# Sheet1.net
KiCad netlist of a schematic drawn in Altium Designer
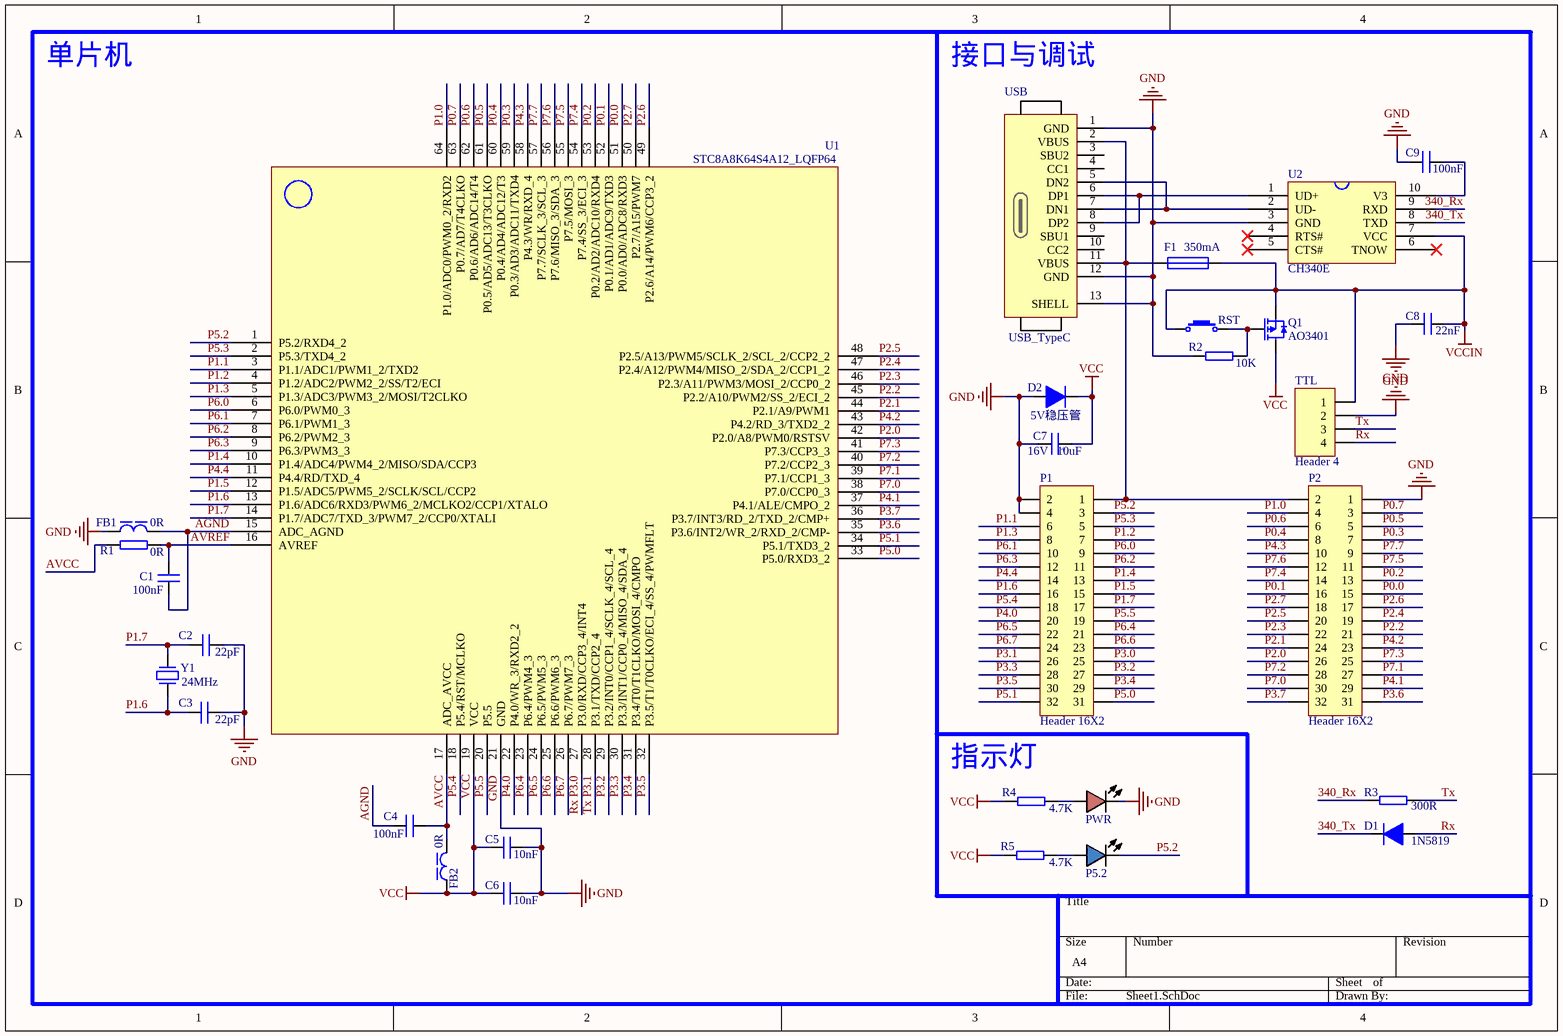
[diagram p0: Sheet1.SchDoc]

(export (version "E")
  (design (tool "Eeschema 10.0.6"))
  (components
    (comp (ref "C1")
      (value "100nF")
      (footprint "0603电容")
      (description "电容")
      (fields (field (name "版权归属") "源创客"))
      (libsource (lib "Schlib1") (part "Capacitor"))
    )
    (comp (ref "C2")
      (value "22pF")
      (footprint "0603电容")
      (description "电容")
      (fields (field (name "版权归属") "源创客"))
      (libsource (lib "Schlib1") (part "Capacitor"))
    )
    (comp (ref "C3")
      (value "22pF")
      (footprint "0603电容")
      (description "电容")
      (fields (field (name "版权归属") "源创客"))
      (libsource (lib "Schlib1") (part "Capacitor"))
    )
    (comp (ref "C4")
      (value "100nF")
      (footprint "0603电容")
      (description "电容")
      (fields (field (name "版权归属") "源创客"))
      (libsource (lib "Schlib1") (part "Capacitor"))
    )
    (comp (ref "C5")
      (value "10nF")
      (footprint "0603电容")
      (description "电容")
      (fields (field (name "版权归属") "源创客"))
      (libsource (lib "Schlib1") (part "Capacitor"))
    )
    (comp (ref "C6")
      (value "10nF")
      (footprint "0603电容")
      (description "电容")
      (fields (field (name "版权归属") "源创客"))
      (libsource (lib "Schlib1") (part "Capacitor"))
    )
    (comp (ref "C7")
      (value "16V   10uF")
      (footprint "Tan1206")
      (description "贴片钽电容")
      (fields (field (name "版权归属") "源创客"))
      (libsource (lib "Schlib1") (part "T_Capacitor"))
    )
    (comp (ref "C8")
      (value "22nF")
      (footprint "0603电容")
      (description "电容")
      (fields (field (name "版权归属") "源创客"))
      (libsource (lib "Schlib1") (part "Capacitor"))
    )
    (comp (ref "C9")
      (value "100nF")
      (footprint "0603电容")
      (description "电容")
      (fields (field (name "版权归属") "源创客"))
      (libsource (lib "Schlib1") (part "Capacitor"))
    )
    (comp (ref "D1") (value "1N5819") (footprint "SOD-323") (libsource (lib "Schlib1") (part "1N5819")))
    (comp (ref "D2") (value "5V稳压管") (footprint "SOD-323") (libsource (lib "Schlib1") (part "5V稳压管")))
    (comp (ref "F1")
      (value "350mA")
      (footprint "0603保险丝")
      (description "Fuse")
      (libsource (lib "Schlib1") (part "Fuse"))
    )
    (comp (ref "FB1")
      (value "0R")
      (footprint "0603磁珠")
      (description "磁珠")
      (libsource (lib "Schlib1") (part "FERRITE_BEAD"))
    )
    (comp (ref "FB2")
      (value "0R")
      (footprint "0603磁珠")
      (description "磁珠")
      (libsource (lib "Schlib1") (part "FERRITE_BEAD"))
    )
    (comp (ref "P1")
      (value "Header 16X2")
      (footprint "HDR-16X2")
      (description "16*2P接插件")
      (fields (field (name "版权归属") "源创客"))
      (libsource (lib "Schlib1") (part "Header 16X2"))
    )
    (comp (ref "P2")
      (value "Header 16X2")
      (footprint "HDR-16X2")
      (description "16*2P接插件")
      (fields (field (name "版权归属") "源创客"))
      (libsource (lib "Schlib1") (part "Header 16X2"))
    )
    (comp (ref "P5.2")
      (value "Blue_LED")
      (footprint "LED 0603B")
      (libsource (lib "Schlib1") (part "Blue_LED"))
    )
    (comp (ref "PWR") (value "Red_LED") (footprint "LED 0603R") (libsource (lib "Schlib1") (part "Red_LED")))
    (comp (ref "Q1")
      (value "AO3401")
      (footprint "SOT-23")
      (fields (field (name "版权归属") "源创客"))
      (libsource (lib "Schlib1") (part "AO3401"))
    )
    (comp (ref "R1")
      (value "0R")
      (footprint "0603电阻")
      (description "电阻")
      (fields (field (name "版权归属") "源创客"))
      (libsource (lib "Schlib1") (part "Resistor"))
    )
    (comp (ref "R2")
      (value "10K")
      (footprint "0603电阻")
      (description "电阻")
      (fields (field (name "版权归属") "源创客"))
      (libsource (lib "Schlib1") (part "Resistor"))
    )
    (comp (ref "R3")
      (value "300R")
      (footprint "0603电阻")
      (description "电阻")
      (fields (field (name "版权归属") "源创客"))
      (libsource (lib "Schlib1") (part "Resistor"))
    )
    (comp (ref "R4")
      (value "4.7K")
      (footprint "0603电阻")
      (description "电阻")
      (fields (field (name "版权归属") "源创客"))
      (libsource (lib "Schlib1") (part "Resistor"))
    )
    (comp (ref "R5")
      (value "4.7K")
      (footprint "0603电阻")
      (description "电阻")
      (fields (field (name "版权归属") "源创客"))
      (libsource (lib "Schlib1") (part "Resistor"))
    )
    (comp (ref "RST")
      (value "*")
      (footprint "SWD")
      (description "轻触开关")
      (libsource (lib "Schlib1") (part "SW_TB"))
    )
    (comp (ref "TTL")
      (value "Header 4")
      (footprint "HDR-1X4")
      (description "4P接插件")
      (fields (field (name "版权归属") "源创客"))
      (libsource (lib "Schlib1") (part "Header 4"))
    )
    (comp (ref "U1")
      (value "STC8A8K64S4A12_LQFP64")
      (footprint "LQFP64-10*10")
      (libsource (lib "Schlib1") (part "STC8A8K64S4A12_LQFP64"))
    )
    (comp (ref "U2") (value "CH340E") (footprint "MSOP-10") (libsource (lib "Schlib1") (part "CH340E")))
    (comp (ref "USB")
      (value "USB_TypeC")
      (footprint "USB3.1 TypeC")
      (description "TypeC接口")
      (libsource (lib "Schlib1") (part "USB3.1"))
    )
    (comp (ref "Y1")
      (value "24MHz")
      (footprint "XTAL-SMD3225")
      (description "晶振")
      (fields (field (name "版权归属") "源创客"))
      (libsource (lib "Schlib1") (part "Crystal"))
    )
  )
  (nets
    (net (code "1") (name "/340_Rx") (class "Default")
      (node (ref "R3") (pin "1") (pinfunction "1_1") (pintype "passive"))
      (node (ref "U2") (pin "9") (pinfunction "RXD_9") (pintype "power_in"))
    )
    (net (code "2") (name "/340_Tx") (class "Default")
      (node (ref "D1") (pin "1") (pinfunction "1_1") (pintype "passive"))
      (node (ref "U2") (pin "8") (pinfunction "TXD_8") (pintype "power_in"))
    )
    (net (code "3") (name "/AGND") (class "Default")
      (node (ref "C1") (pin "2") (pinfunction "2_2") (pintype "passive"))
      (node (ref "C4") (pin "1") (pinfunction "1_1") (pintype "passive"))
      (node (ref "FB1") (pin "2") (pinfunction "2_2") (pintype "passive"))
      (node (ref "U1") (pin "15") (pinfunction "ADC_AGND_15") (pintype "passive"))
    )
    (net (code "4") (name "/AVCC") (class "Default")
      (node (ref "C4") (pin "2") (pinfunction "2_2") (pintype "passive"))
      (node (ref "FB2") (pin "2") (pinfunction "2_2") (pintype "passive"))
      (node (ref "R1") (pin "1") (pinfunction "1_1") (pintype "passive"))
      (node (ref "U1") (pin "17") (pinfunction "ADC_AVCC_17") (pintype "passive"))
    )
    (net (code "5") (name "/AVREF") (class "Default")
      (node (ref "C1") (pin "1") (pinfunction "1_1") (pintype "passive"))
      (node (ref "R1") (pin "2") (pinfunction "2_2") (pintype "passive"))
      (node (ref "U1") (pin "16") (pinfunction "AVREF_16") (pintype "passive"))
    )
    (net (code "6") (name "/P0.0") (class "Default")
      (node (ref "P2") (pin "15") (pinfunction "15_15") (pintype "passive"))
      (node (ref "U1") (pin "51") (pinfunction "P0.0/AD0/ADC8/RXD3_51") (pintype "passive"))
    )
    (net (code "7") (name "/P0.1") (class "Default")
      (node (ref "P2") (pin "16") (pinfunction "16_16") (pintype "passive"))
      (node (ref "U1") (pin "52") (pinfunction "P0.1/AD1/ADC9/TXD3_52") (pintype "passive"))
    )
    (net (code "8") (name "/P0.2") (class "Default")
      (node (ref "P2") (pin "13") (pinfunction "13_13") (pintype "passive"))
      (node (ref "U1") (pin "53") (pinfunction "P0.2/AD2/ADC10/RXD4_53") (pintype "passive"))
    )
    (net (code "9") (name "/P0.3") (class "Default")
      (node (ref "P2") (pin "7") (pinfunction "7_7") (pintype "passive"))
      (node (ref "U1") (pin "59") (pinfunction "P0.3/AD3/ADC11/TXD4_59") (pintype "passive"))
    )
    (net (code "10") (name "/P0.4") (class "Default")
      (node (ref "P2") (pin "8") (pinfunction "8_8") (pintype "passive"))
      (node (ref "U1") (pin "60") (pinfunction "P0.4/AD4/ADC12/T3_60") (pintype "passive"))
    )
    (net (code "11") (name "/P0.5") (class "Default")
      (node (ref "P2") (pin "5") (pinfunction "5_5") (pintype "passive"))
      (node (ref "U1") (pin "61") (pinfunction "P0.5/AD5/ADC13/T3CLKO_61") (pintype "passive"))
    )
    (net (code "12") (name "/P0.6") (class "Default")
      (node (ref "P2") (pin "6") (pinfunction "6_6") (pintype "passive"))
      (node (ref "U1") (pin "62") (pinfunction "P0.6/AD6/ADC14/T4_62") (pintype "passive"))
    )
    (net (code "13") (name "/P0.7") (class "Default")
      (node (ref "P2") (pin "3") (pinfunction "3_3") (pintype "passive"))
      (node (ref "U1") (pin "63") (pinfunction "P0.7/AD7/T4CLKO_63") (pintype "passive"))
    )
    (net (code "14") (name "/P1.0") (class "Default")
      (node (ref "P2") (pin "4") (pinfunction "4_4") (pintype "passive"))
      (node (ref "U1") (pin "64") (pinfunction "P1.0/ADC0/PWM0_2/RXD2_64") (pintype "passive"))
    )
    (net (code "15") (name "/P1.1") (class "Default")
      (node (ref "P1") (pin "6") (pinfunction "6_6") (pintype "passive"))
      (node (ref "U1") (pin "3") (pinfunction "P1.1/ADC1/PWM1_2/TXD2_3") (pintype "passive"))
    )
    (net (code "16") (name "/P1.2") (class "Default")
      (node (ref "P1") (pin "7") (pinfunction "7_7") (pintype "passive"))
      (node (ref "U1") (pin "4") (pinfunction "P1.2/ADC2/PWM2_2/SS/T2/ECI_4") (pintype "passive"))
    )
    (net (code "17") (name "/P1.3") (class "Default")
      (node (ref "P1") (pin "8") (pinfunction "8_8") (pintype "passive"))
      (node (ref "U1") (pin "5") (pinfunction "P1.3/ADC3/PWM3_2/MOSI/T2CLKO_5") (pintype "passive"))
    )
    (net (code "18") (name "/P1.4") (class "Default")
      (node (ref "P1") (pin "13") (pinfunction "13_13") (pintype "passive"))
      (node (ref "U1") (pin "10") (pinfunction "P1.4/ADC4/PWM4_2/MISO/SDA/CCP3_10") (pintype "passive"))
    )
    (net (code "19") (name "/P1.5") (class "Default")
      (node (ref "P1") (pin "15") (pinfunction "15_15") (pintype "passive"))
      (node (ref "U1") (pin "12") (pinfunction "P1.5/ADC5/PWM5_2/SCLK/SCL/CCP2_12") (pintype "passive"))
    )
    (net (code "20") (name "/P1.6") (class "Default")
      (node (ref "C3") (pin "1") (pinfunction "1_1") (pintype "passive"))
      (node (ref "P1") (pin "16") (pinfunction "16_16") (pintype "passive"))
      (node (ref "U1") (pin "13") (pinfunction "P1.6/ADC6/RXD3/PWM6_2/MCLKO2/CCP1/XTALO_13") (pintype "passive"))
      (node (ref "Y1") (pin "1") (pinfunction "1_1") (pintype "passive"))
    )
    (net (code "21") (name "/P1.7") (class "Default")
      (node (ref "C2") (pin "1") (pinfunction "1_1") (pintype "passive"))
      (node (ref "P1") (pin "17") (pinfunction "17_17") (pintype "passive"))
      (node (ref "U1") (pin "14") (pinfunction "P1.7/ADC7/TXD_3/PWM7_2/CCP0/XTALI_14") (pintype "passive"))
      (node (ref "Y1") (pin "3") (pinfunction "3_3") (pintype "passive"))
    )
    (net (code "22") (name "/P2.0") (class "Default")
      (node (ref "P2") (pin "26") (pinfunction "26_26") (pintype "passive"))
      (node (ref "U1") (pin "42") (pinfunction "P2.0/A8/PWM0/RSTSV_42") (pintype "passive"))
    )
    (net (code "23") (name "/P2.1") (class "Default")
      (node (ref "P2") (pin "24") (pinfunction "24_24") (pintype "passive"))
      (node (ref "U1") (pin "44") (pinfunction "P2.1/A9/PWM1_44") (pintype "passive"))
    )
    (net (code "24") (name "/P2.2") (class "Default")
      (node (ref "P2") (pin "21") (pinfunction "21_21") (pintype "passive"))
      (node (ref "U1") (pin "45") (pinfunction "P2.2/A10/PWM2/SS_2/ECI_2_45") (pintype "passive"))
    )
    (net (code "25") (name "/P2.3") (class "Default")
      (node (ref "P2") (pin "22") (pinfunction "22_22") (pintype "passive"))
      (node (ref "U1") (pin "46") (pinfunction "P2.3/A11/PWM3/MOSI_2/CCP0_2_46") (pintype "passive"))
    )
    (net (code "26") (name "/P2.4") (class "Default")
      (node (ref "P2") (pin "19") (pinfunction "19_19") (pintype "passive"))
      (node (ref "U1") (pin "47") (pinfunction "P2.4/A12/PWM4/MISO_2/SDA_2/CCP1_2_47") (pintype "passive"))
    )
    (net (code "27") (name "/P2.5") (class "Default")
      (node (ref "P2") (pin "20") (pinfunction "20_20") (pintype "passive"))
      (node (ref "U1") (pin "48") (pinfunction "P2.5/A13/PWM5/SCLK_2/SCL_2/CCP2_2_48") (pintype "passive"))
    )
    (net (code "28") (name "/P2.6") (class "Default")
      (node (ref "P2") (pin "17") (pinfunction "17_17") (pintype "passive"))
      (node (ref "U1") (pin "49") (pinfunction "P2.6/A14/PWM6/CCP3_2_49") (pintype "passive"))
    )
    (net (code "29") (name "/P2.7") (class "Default")
      (node (ref "P2") (pin "18") (pinfunction "18_18") (pintype "passive"))
      (node (ref "U1") (pin "50") (pinfunction "P2.7/A15/PWM7_50") (pintype "passive"))
    )
    (net (code "30") (name "/P3.0") (class "Default")
      (node (ref "D1") (pin "2") (pinfunction "2_2") (pintype "passive"))
      (node (ref "P1") (pin "25") (pinfunction "25_25") (pintype "passive"))
      (node (ref "TTL") (pin "4") (pinfunction "4_4") (pintype "passive"))
      (node (ref "U1") (pin "27") (pinfunction "P3.0/RXD/CCP3_4/INT4_27") (pintype "passive"))
    )
    (net (code "31") (name "/P3.1") (class "Default")
      (node (ref "P1") (pin "26") (pinfunction "26_26") (pintype "passive"))
      (node (ref "R3") (pin "2") (pinfunction "2_2") (pintype "passive"))
      (node (ref "TTL") (pin "3") (pinfunction "3_3") (pintype "passive"))
      (node (ref "U1") (pin "28") (pinfunction "P3.1/TXD/CCP2_4_28") (pintype "passive"))
    )
    (net (code "32") (name "/P3.2") (class "Default")
      (node (ref "P1") (pin "27") (pinfunction "27_27") (pintype "passive"))
      (node (ref "U1") (pin "29") (pinfunction "P3.2/INT0/CCP1_4/SCLK_4/SCL_4_29") (pintype "passive"))
    )
    (net (code "33") (name "/P3.3") (class "Default")
      (node (ref "P1") (pin "28") (pinfunction "28_28") (pintype "passive"))
      (node (ref "U1") (pin "30") (pinfunction "P3.3/INT1/CCP0_4/MISO_4/SDA_4_30") (pintype "passive"))
    )
    (net (code "34") (name "/P3.4") (class "Default")
      (node (ref "P1") (pin "29") (pinfunction "29_29") (pintype "passive"))
      (node (ref "U1") (pin "31") (pinfunction "P3.4/T0/T1CLKO/MOSI_4/CMPO_31") (pintype "passive"))
    )
    (net (code "35") (name "/P3.5") (class "Default")
      (node (ref "P1") (pin "30") (pinfunction "30_30") (pintype "passive"))
      (node (ref "U1") (pin "32") (pinfunction "P3.5/T1/T0CLKO/ECI_4/SS_4/PWMFLT_32") (pintype "passive"))
    )
    (net (code "36") (name "/P3.6") (class "Default")
      (node (ref "P2") (pin "31") (pinfunction "31_31") (pintype "passive"))
      (node (ref "U1") (pin "35") (pinfunction "P3.6/INT2/WR_2/RXD_2/CMP-_35") (pintype "passive"))
    )
    (net (code "37") (name "/P3.7") (class "Default")
      (node (ref "P2") (pin "32") (pinfunction "32_32") (pintype "passive"))
      (node (ref "U1") (pin "36") (pinfunction "P3.7/INT3/RD_2/TXD_2/CMP+_36") (pintype "passive"))
    )
    (net (code "38") (name "/P4.0") (class "Default")
      (node (ref "P1") (pin "20") (pinfunction "20_20") (pintype "passive"))
      (node (ref "U1") (pin "22") (pinfunction "P4.0/WR_3/RXD2_2_22") (pintype "passive"))
    )
    (net (code "39") (name "/P4.1") (class "Default")
      (node (ref "P2") (pin "29") (pinfunction "29_29") (pintype "passive"))
      (node (ref "U1") (pin "37") (pinfunction "P4.1/ALE/CMPO_2_37") (pintype "passive"))
    )
    (net (code "40") (name "/P4.2") (class "Default")
      (node (ref "P2") (pin "23") (pinfunction "23_23") (pintype "passive"))
      (node (ref "U1") (pin "43") (pinfunction "P4.2/RD_3/TXD2_2_43") (pintype "passive"))
    )
    (net (code "41") (name "/P4.3") (class "Default")
      (node (ref "P2") (pin "10") (pinfunction "10_10") (pintype "passive"))
      (node (ref "U1") (pin "58") (pinfunction "P4.3/WR/RXD_4_58") (pintype "passive"))
    )
    (net (code "42") (name "/P4.4") (class "Default")
      (node (ref "P1") (pin "14") (pinfunction "14_14") (pintype "passive"))
      (node (ref "U1") (pin "11") (pinfunction "P4.4/RD/TXD_4_11") (pintype "passive"))
    )
    (net (code "43") (name "/P5.0") (class "Default")
      (node (ref "P1") (pin "31") (pinfunction "31_31") (pintype "passive"))
      (node (ref "U1") (pin "33") (pinfunction "P5.0/RXD3_2_33") (pintype "passive"))
    )
    (net (code "44") (name "/P5.1") (class "Default")
      (node (ref "P1") (pin "32") (pinfunction "32_32") (pintype "passive"))
      (node (ref "U1") (pin "34") (pinfunction "P5.1/TXD3_2_34") (pintype "passive"))
    )
    (net (code "45") (name "/P5.2") (class "Default")
      (node (ref "P1") (pin "3") (pinfunction "3_3") (pintype "passive"))
      (node (ref "P5.2") (pin "2") (pinfunction "2_2") (pintype "passive"))
      (node (ref "U1") (pin "1") (pinfunction "P5.2/RXD4_2_1") (pintype "passive"))
    )
    (net (code "46") (name "/P5.3") (class "Default")
      (node (ref "P1") (pin "5") (pinfunction "5_5") (pintype "passive"))
      (node (ref "U1") (pin "2") (pinfunction "P5.3/TXD4_2_2") (pintype "passive"))
    )
    (net (code "47") (name "/P5.4") (class "Default")
      (node (ref "P1") (pin "18") (pinfunction "18_18") (pintype "passive"))
      (node (ref "U1") (pin "18") (pinfunction "P5.4/RST/MCLKO_18") (pintype "passive"))
    )
    (net (code "48") (name "/P5.5") (class "Default")
      (node (ref "P1") (pin "19") (pinfunction "19_19") (pintype "passive"))
      (node (ref "U1") (pin "20") (pinfunction "P5.5_20") (pintype "passive"))
    )
    (net (code "49") (name "/P6.0") (class "Default")
      (node (ref "P1") (pin "9") (pinfunction "9_9") (pintype "passive"))
      (node (ref "U1") (pin "6") (pinfunction "P6.0/PWM0_3_6") (pintype "passive"))
    )
    (net (code "50") (name "/P6.1") (class "Default")
      (node (ref "P1") (pin "10") (pinfunction "10_10") (pintype "passive"))
      (node (ref "U1") (pin "7") (pinfunction "P6.1/PWM1_3_7") (pintype "passive"))
    )
    (net (code "51") (name "/P6.2") (class "Default")
      (node (ref "P1") (pin "11") (pinfunction "11_11") (pintype "passive"))
      (node (ref "U1") (pin "8") (pinfunction "P6.2/PWM2_3_8") (pintype "passive"))
    )
    (net (code "52") (name "/P6.3") (class "Default")
      (node (ref "P1") (pin "12") (pinfunction "12_12") (pintype "passive"))
      (node (ref "U1") (pin "9") (pinfunction "P6.3/PWM3_3_9") (pintype "passive"))
    )
    (net (code "53") (name "/P6.4") (class "Default")
      (node (ref "P1") (pin "21") (pinfunction "21_21") (pintype "passive"))
      (node (ref "U1") (pin "23") (pinfunction "P6.4/PWM4_3_23") (pintype "passive"))
    )
    (net (code "54") (name "/P6.5") (class "Default")
      (node (ref "P1") (pin "22") (pinfunction "22_22") (pintype "passive"))
      (node (ref "U1") (pin "24") (pinfunction "P6.5/PWM5_3_24") (pintype "passive"))
    )
    (net (code "55") (name "/P6.6") (class "Default")
      (node (ref "P1") (pin "23") (pinfunction "23_23") (pintype "passive"))
      (node (ref "U1") (pin "25") (pinfunction "P6.6/PWM6_3_25") (pintype "passive"))
    )
    (net (code "56") (name "/P6.7") (class "Default")
      (node (ref "P1") (pin "24") (pinfunction "24_24") (pintype "passive"))
      (node (ref "U1") (pin "26") (pinfunction "P6.7/PWM7_3_26") (pintype "passive"))
    )
    (net (code "57") (name "/P7.0") (class "Default")
      (node (ref "P2") (pin "30") (pinfunction "30_30") (pintype "passive"))
      (node (ref "U1") (pin "38") (pinfunction "P7.0/CCP0_3_38") (pintype "passive"))
    )
    (net (code "58") (name "/P7.1") (class "Default")
      (node (ref "P2") (pin "27") (pinfunction "27_27") (pintype "passive"))
      (node (ref "U1") (pin "39") (pinfunction "P7.1/CCP1_3_39") (pintype "passive"))
    )
    (net (code "59") (name "/P7.2") (class "Default")
      (node (ref "P2") (pin "28") (pinfunction "28_28") (pintype "passive"))
      (node (ref "U1") (pin "40") (pinfunction "P7.2/CCP2_3_40") (pintype "passive"))
    )
    (net (code "60") (name "/P7.3") (class "Default")
      (node (ref "P2") (pin "25") (pinfunction "25_25") (pintype "passive"))
      (node (ref "U1") (pin "41") (pinfunction "P7.3/CCP3_3_41") (pintype "passive"))
    )
    (net (code "61") (name "/P7.4") (class "Default")
      (node (ref "P2") (pin "14") (pinfunction "14_14") (pintype "passive"))
      (node (ref "U1") (pin "54") (pinfunction "P7.4/SS_3/ECI_3_54") (pintype "passive"))
    )
    (net (code "62") (name "/P7.5") (class "Default")
      (node (ref "P2") (pin "11") (pinfunction "11_11") (pintype "passive"))
      (node (ref "U1") (pin "55") (pinfunction "P7.5/MOSI_3_55") (pintype "passive"))
    )
    (net (code "63") (name "/P7.6") (class "Default")
      (node (ref "P2") (pin "12") (pinfunction "12_12") (pintype "passive"))
      (node (ref "U1") (pin "56") (pinfunction "P7.6/MISO_3/SDA_3_56") (pintype "passive"))
    )
    (net (code "64") (name "/P7.7") (class "Default")
      (node (ref "P2") (pin "9") (pinfunction "9_9") (pintype "passive"))
      (node (ref "U1") (pin "57") (pinfunction "P7.7/SCLK_3/SCL_3_57") (pintype "passive"))
    )
    (net (code "65") (name "GND") (class "Default")
      (node (ref "C2") (pin "2") (pinfunction "2_2") (pintype "passive"))
      (node (ref "C3") (pin "2") (pinfunction "2_2") (pintype "passive"))
      (node (ref "C5") (pin "2") (pinfunction "2_2") (pintype "passive"))
      (node (ref "C6") (pin "2") (pinfunction "2_2") (pintype "passive"))
      (node (ref "C7") (pin "2") (pinfunction "K_2") (pintype "passive"))
      (node (ref "C8") (pin "1") (pinfunction "1_1") (pintype "passive"))
      (node (ref "C9") (pin "1") (pinfunction "1_1") (pintype "passive"))
      (node (ref "D2") (pin "2") (pinfunction "2_2") (pintype "passive"))
      (node (ref "FB1") (pin "1") (pinfunction "1_1") (pintype "passive"))
      (node (ref "P1") (pin "2") (pinfunction "2_2") (pintype "passive"))
      (node (ref "P1") (pin "4") (pinfunction "4_4") (pintype "passive"))
      (node (ref "P2") (pin "1") (pinfunction "1_1") (pintype "passive"))
      (node (ref "PWR") (pin "2") (pinfunction "2_2") (pintype "passive"))
      (node (ref "R2") (pin "1") (pinfunction "1_1") (pintype "passive"))
      (node (ref "TTL") (pin "2") (pinfunction "2_2") (pintype "passive"))
      (node (ref "U1") (pin "21") (pinfunction "GND_21") (pintype "passive"))
      (node (ref "U2") (pin "3") (pinfunction "GND_3") (pintype "passive"))
      (node (ref "USB") (pin "1") (pinfunction "GND_1") (pintype "passive"))
      (node (ref "USB") (pin "12") (pinfunction "GND_12") (pintype "passive"))
      (node (ref "USB") (pin "13") (pinfunction "SHELL_13") (pintype "passive"))
    )
    (net (code "66") (name "Net-(F1-Pad1)") (class "Default")
      (node (ref "F1") (pin "1") (pinfunction "1_1") (pintype "passive"))
      (node (ref "P1") (pin "1") (pinfunction "1_1") (pintype "passive"))
      (node (ref "P2") (pin "2") (pinfunction "2_2") (pintype "passive"))
      (node (ref "USB") (pin "11") (pinfunction "VBUS_11") (pintype "passive"))
      (node (ref "USB") (pin "2") (pinfunction "VBUS_2") (pintype "passive"))
    )
    (net (code "67") (name "Net-(P5.2-Pad1)") (class "Default")
      (node (ref "P5.2") (pin "1") (pinfunction "1_1") (pintype "passive"))
      (node (ref "R5") (pin "2") (pinfunction "2_2") (pintype "passive"))
    )
    (net (code "68") (name "Net-(PWR-Pad1)") (class "Default")
      (node (ref "PWR") (pin "1") (pinfunction "1_1") (pintype "passive"))
      (node (ref "R4") (pin "2") (pinfunction "2_2") (pintype "passive"))
    )
    (net (code "69") (name "Net-(Q1-Pad1)") (class "Default")
      (node (ref "Q1") (pin "1") (pinfunction "1_1") (pintype "passive"))
      (node (ref "R2") (pin "2") (pinfunction "2_2") (pintype "passive"))
      (node (ref "RST") (pin "2") (pinfunction "2_2") (pintype "passive"))
    )
    (net (code "70") (name "Net-(U2-UD+)") (class "Default")
      (node (ref "U2") (pin "1") (pinfunction "UD+_1") (pintype "passive"))
      (node (ref "USB") (pin "6") (pinfunction "DP1_6") (pintype "passive"))
      (node (ref "USB") (pin "8") (pinfunction "DP2_8") (pintype "passive"))
    )
    (net (code "71") (name "Net-(U2-UD-)") (class "Default")
      (node (ref "U2") (pin "2") (pinfunction "UD-_2") (pintype "passive"))
      (node (ref "USB") (pin "5") (pinfunction "DN2_5") (pintype "passive"))
      (node (ref "USB") (pin "7") (pinfunction "DN1_7") (pintype "passive"))
    )
    (net (code "72") (name "Net-(U2-V3)") (class "Default")
      (node (ref "C9") (pin "2") (pinfunction "2_2") (pintype "passive"))
      (node (ref "U2") (pin "10") (pinfunction "V3_10") (pintype "passive"))
    )
    (net (code "73") (name "VCC") (class "Default")
      (node (ref "C5") (pin "1") (pinfunction "1_1") (pintype "passive"))
      (node (ref "C6") (pin "1") (pinfunction "1_1") (pintype "passive"))
      (node (ref "C7") (pin "1") (pinfunction "A_1") (pintype "passive"))
      (node (ref "D2") (pin "1") (pinfunction "1_1") (pintype "passive"))
      (node (ref "FB2") (pin "1") (pinfunction "1_1") (pintype "passive"))
      (node (ref "Q1") (pin "2") (pinfunction "2_2") (pintype "passive"))
      (node (ref "R4") (pin "1") (pinfunction "1_1") (pintype "passive"))
      (node (ref "R5") (pin "1") (pinfunction "1_1") (pintype "passive"))
      (node (ref "U1") (pin "19") (pinfunction "VCC_19") (pintype "passive"))
    )
    (net (code "74") (name "VCCIN") (class "Default")
      (node (ref "C8") (pin "2") (pinfunction "2_2") (pintype "passive"))
      (node (ref "F1") (pin "2") (pinfunction "2_2") (pintype "passive"))
      (node (ref "Q1") (pin "3") (pinfunction "3_3") (pintype "passive"))
      (node (ref "RST") (pin "1") (pinfunction "1_1") (pintype "passive"))
      (node (ref "TTL") (pin "1") (pinfunction "1_1") (pintype "passive"))
      (node (ref "U2") (pin "7") (pinfunction "VCC_7") (pintype "passive"))
    )
    (net (code "75") (name "unconnected-(U2-CTS#-Pad5)") (class "Default")
      (node (ref "U2") (pin "5") (pinfunction "CTS#_5") (pintype "passive+no_connect"))
    )
    (net (code "76") (name "unconnected-(U2-RTS#-Pad4)") (class "Default")
      (node (ref "U2") (pin "4") (pinfunction "RTS#_4") (pintype "passive+no_connect"))
    )
    (net (code "77") (name "unconnected-(U2-TNOW-Pad6)") (class "Default")
      (node (ref "U2") (pin "6") (pinfunction "TNOW_6") (pintype "passive+no_connect"))
    )
    (net (code "78") (name "unconnected-(USB-CC1-Pad4)") (class "Default")
      (node (ref "USB") (pin "4") (pinfunction "CC1_4") (pintype "passive"))
    )
    (net (code "79") (name "unconnected-(USB-CC2-Pad10)") (class "Default")
      (node (ref "USB") (pin "10") (pinfunction "CC2_10") (pintype "passive"))
    )
    (net (code "80") (name "unconnected-(USB-SBU1-Pad9)") (class "Default")
      (node (ref "USB") (pin "9") (pinfunction "SBU1_9") (pintype "passive"))
    )
    (net (code "81") (name "unconnected-(USB-SBU2-Pad3)") (class "Default")
      (node (ref "USB") (pin "3") (pinfunction "SBU2_3") (pintype "passive"))
    )
  )
)
